# 3_FPGA.net
KiCad netlist of a schematic drawn in Altium Designer
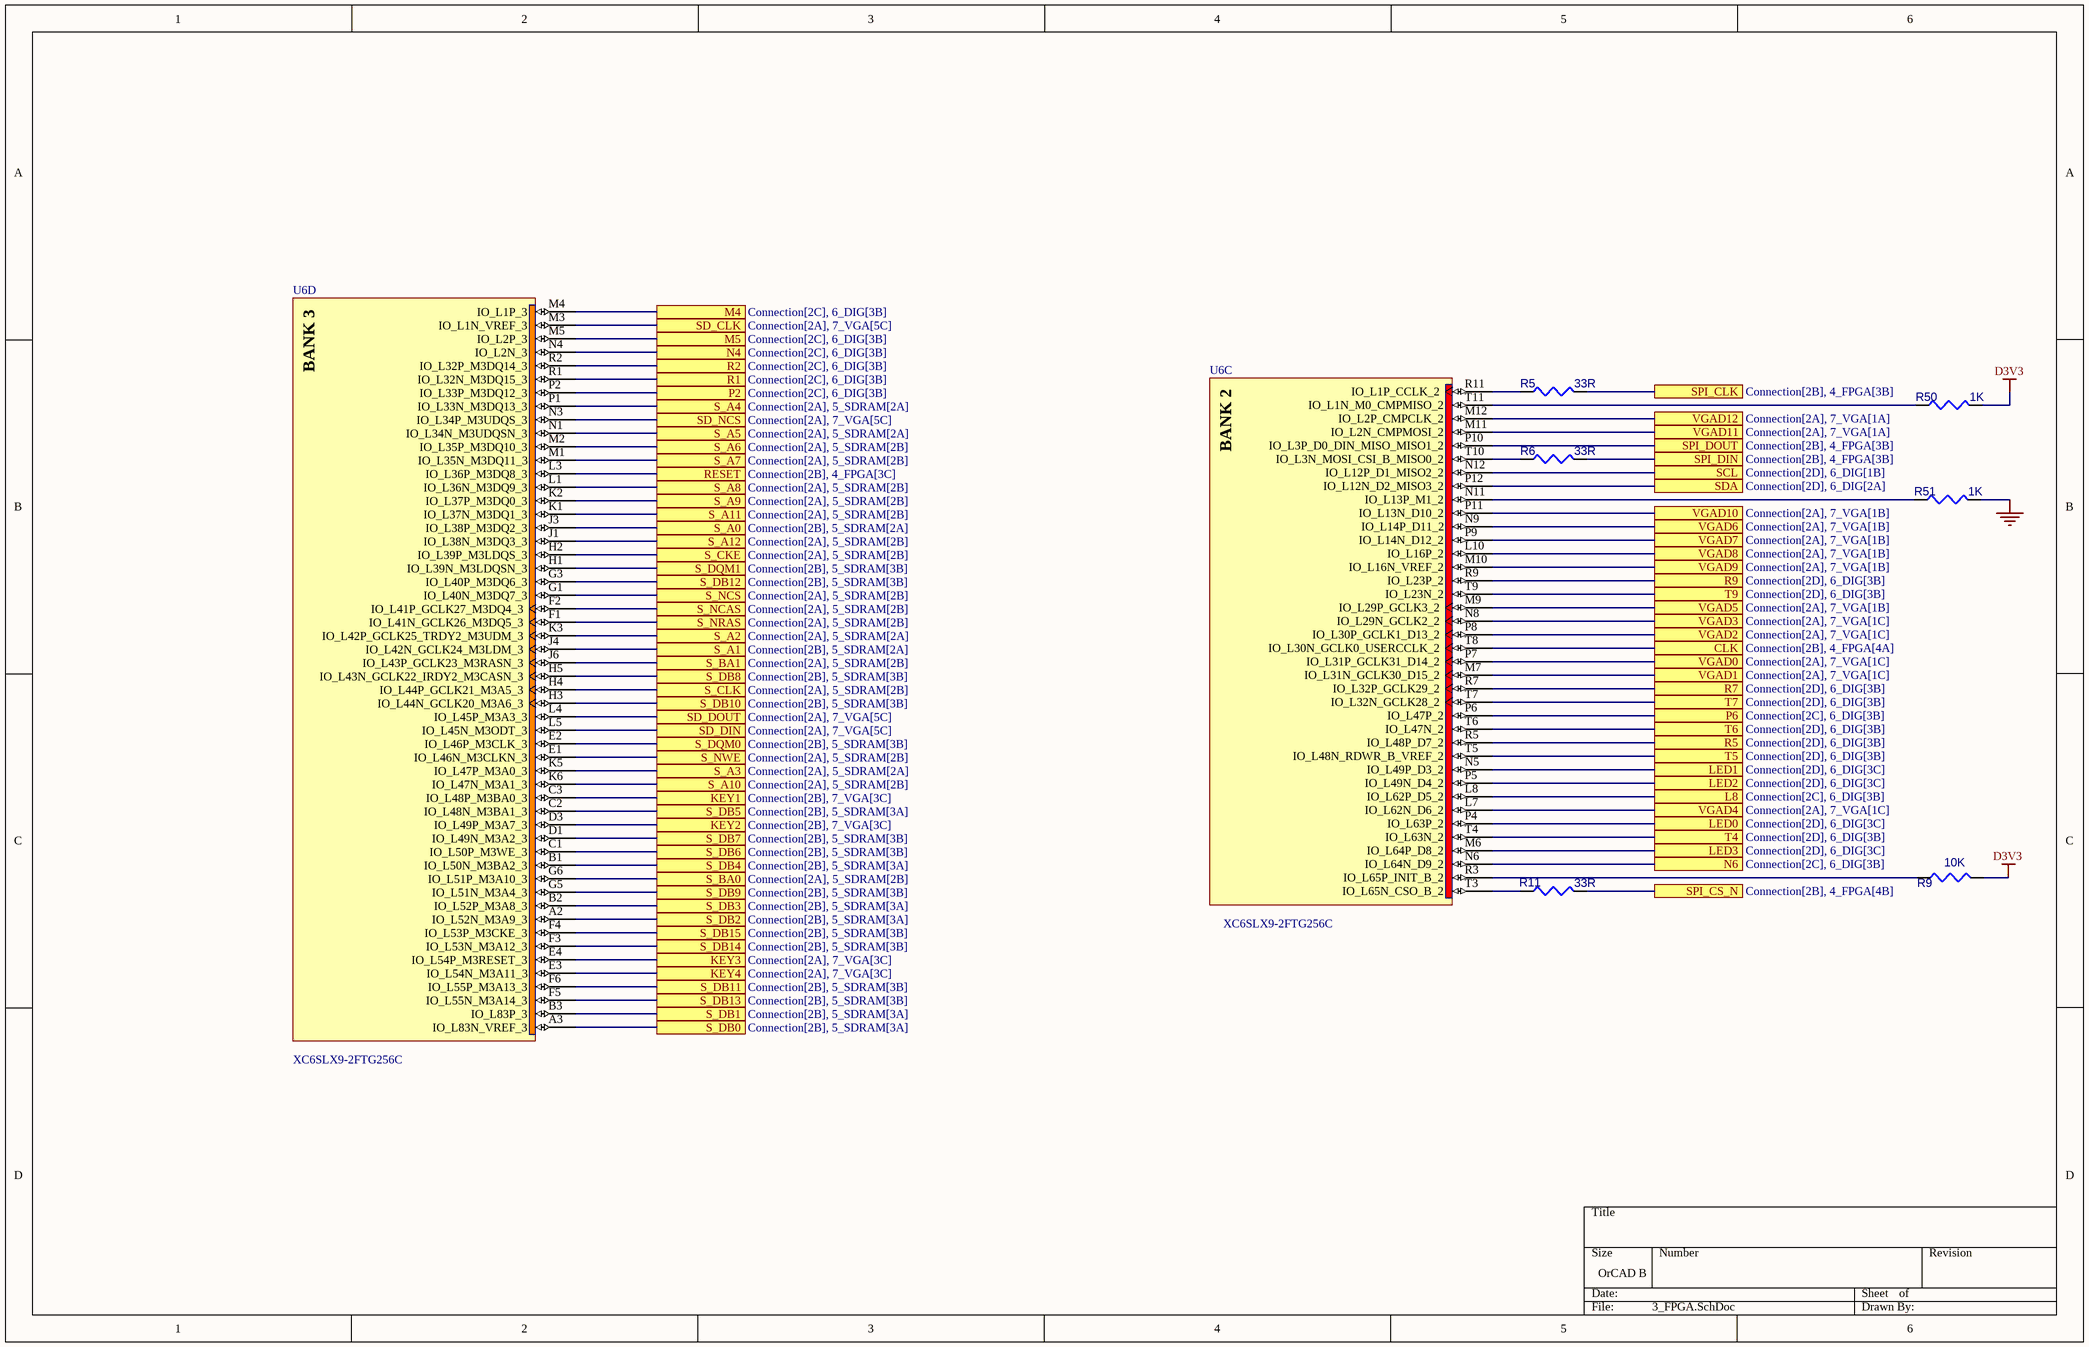
[diagram p0: 3_FPGA.SchDoc]

(export (version "E")
  (design (tool "Eeschema 10.0.6"))
  (components
    (comp (ref "R5") (value "33R") (footprint "0603") (libsource (lib "*") (part "R_Dup3")))
    (comp (ref "R6") (value "33R") (footprint "0603") (libsource (lib "*") (part "R_Dup3")))
    (comp (ref "R9") (value "10K") (footprint "0603") (libsource (lib "*") (part "R_Dup1")))
    (comp (ref "R11") (value "33R") (footprint "0603") (libsource (lib "*") (part "R_Dup3")))
    (comp (ref "R50") (value "1K") (footprint "0603") (libsource (lib "*") (part "R")))
    (comp (ref "R51") (value "1K") (footprint "0603") (libsource (lib "*") (part "R")))
    (comp (ref "U6")
      (value "XC6SLX9-2FTG256C")
      (footprint "FTG256")
      (libsource (lib "Xilinx Spartan-6") (part "XC6SLX9-2FTG256C"))
    )
  )
  (nets
    (net (code "1") (name "/CLK") (class "Default")
      (node (ref "U6") (pin "T8") (pinfunction "IO_L30N_GCLK0_USERCCLK_2_T8") (pintype "bidirectional"))
    )
    (net (code "2") (name "/KEY1") (class "Default")
      (node (ref "U6") (pin "C3") (pinfunction "IO_L48P_M3BA0_3_C3") (pintype "bidirectional"))
    )
    (net (code "3") (name "/KEY2") (class "Default")
      (node (ref "U6") (pin "D3") (pinfunction "IO_L49P_M3A7_3_D3") (pintype "bidirectional"))
    )
    (net (code "4") (name "/KEY3") (class "Default")
      (node (ref "U6") (pin "E4") (pinfunction "IO_L54P_M3RESET_3_E4") (pintype "bidirectional"))
    )
    (net (code "5") (name "/KEY4") (class "Default")
      (node (ref "U6") (pin "E3") (pinfunction "IO_L54N_M3A11_3_E3") (pintype "bidirectional"))
    )
    (net (code "6") (name "/L8") (class "Default")
      (node (ref "U6") (pin "L8") (pinfunction "IO_L62P_D5_2_L8") (pintype "bidirectional"))
    )
    (net (code "7") (name "/LED0") (class "Default")
      (node (ref "U6") (pin "P4") (pinfunction "IO_L63P_2_P4") (pintype "bidirectional"))
    )
    (net (code "8") (name "/LED1") (class "Default")
      (node (ref "U6") (pin "N5") (pinfunction "IO_L49P_D3_2_N5") (pintype "bidirectional"))
    )
    (net (code "9") (name "/LED2") (class "Default")
      (node (ref "U6") (pin "P5") (pinfunction "IO_L49N_D4_2_P5") (pintype "bidirectional"))
    )
    (net (code "10") (name "/LED3") (class "Default")
      (node (ref "U6") (pin "M6") (pinfunction "IO_L64P_D8_2_M6") (pintype "bidirectional"))
    )
    (net (code "11") (name "/M4") (class "Default")
      (node (ref "U6") (pin "M4") (pinfunction "IO_L1P_3_M4") (pintype "bidirectional"))
    )
    (net (code "12") (name "/M5") (class "Default")
      (node (ref "U6") (pin "M5") (pinfunction "IO_L2P_3_M5") (pintype "bidirectional"))
    )
    (net (code "13") (name "/N4") (class "Default")
      (node (ref "U6") (pin "N4") (pinfunction "IO_L2N_3_N4") (pintype "bidirectional"))
    )
    (net (code "14") (name "/N6") (class "Default")
      (node (ref "U6") (pin "N6") (pinfunction "IO_L64N_D9_2_N6") (pintype "bidirectional"))
    )
    (net (code "15") (name "/P2") (class "Default")
      (node (ref "U6") (pin "P2") (pinfunction "IO_L33P_M3DQ12_3_P2") (pintype "bidirectional"))
    )
    (net (code "16") (name "/P6") (class "Default")
      (node (ref "U6") (pin "P6") (pinfunction "IO_L47P_2_P6") (pintype "bidirectional"))
    )
    (net (code "17") (name "/R1") (class "Default")
      (node (ref "U6") (pin "R1") (pinfunction "IO_L32N_M3DQ15_3_R1") (pintype "bidirectional"))
    )
    (net (code "18") (name "/R2") (class "Default")
      (node (ref "U6") (pin "R2") (pinfunction "IO_L32P_M3DQ14_3_R2") (pintype "bidirectional"))
    )
    (net (code "19") (name "/R5") (class "Default")
      (node (ref "U6") (pin "R5") (pinfunction "IO_L48P_D7_2_R5") (pintype "bidirectional"))
    )
    (net (code "20") (name "/R7") (class "Default")
      (node (ref "U6") (pin "R7") (pinfunction "IO_L32P_GCLK29_2_R7") (pintype "bidirectional"))
    )
    (net (code "21") (name "/R9") (class "Default")
      (node (ref "U6") (pin "R9") (pinfunction "IO_L23P_2_R9") (pintype "bidirectional"))
    )
    (net (code "22") (name "/RESET") (class "Default")
      (node (ref "U6") (pin "L3") (pinfunction "IO_L36P_M3DQ8_3_L3") (pintype "bidirectional"))
    )
    (net (code "23") (name "/SCL") (class "Default")
      (node (ref "U6") (pin "N12") (pinfunction "IO_L12P_D1_MISO2_2_N12") (pintype "bidirectional"))
    )
    (net (code "24") (name "/SDA") (class "Default")
      (node (ref "U6") (pin "P12") (pinfunction "IO_L12N_D2_MISO3_2_P12") (pintype "bidirectional"))
    )
    (net (code "25") (name "/SD_CLK") (class "Default")
      (node (ref "U6") (pin "M3") (pinfunction "IO_L1N_VREF_3_M3") (pintype "bidirectional"))
    )
    (net (code "26") (name "/SD_DIN") (class "Default")
      (node (ref "U6") (pin "L5") (pinfunction "IO_L45N_M3ODT_3_L5") (pintype "bidirectional"))
    )
    (net (code "27") (name "/SD_DOUT") (class "Default")
      (node (ref "U6") (pin "L4") (pinfunction "IO_L45P_M3A3_3_L4") (pintype "bidirectional"))
    )
    (net (code "28") (name "/SD_NCS") (class "Default")
      (node (ref "U6") (pin "N3") (pinfunction "IO_L34P_M3UDQS_3_N3") (pintype "bidirectional"))
    )
    (net (code "29") (name "/SPI_CLK") (class "Default")
      (node (ref "R5") (pin "2") (pinfunction "2_2") (pintype "passive"))
    )
    (net (code "30") (name "/SPI_CS_N") (class "Default")
      (node (ref "R11") (pin "2") (pinfunction "2_2") (pintype "passive"))
    )
    (net (code "31") (name "/SPI_DIN") (class "Default")
      (node (ref "R6") (pin "2") (pinfunction "2_2") (pintype "passive"))
    )
    (net (code "32") (name "/SPI_DOUT") (class "Default")
      (node (ref "U6") (pin "P10") (pinfunction "IO_L3P_D0_DIN_MISO_MISO1_2_P10") (pintype "bidirectional"))
    )
    (net (code "33") (name "/S_A0") (class "Default")
      (node (ref "U6") (pin "J3") (pinfunction "IO_L38P_M3DQ2_3_J3") (pintype "bidirectional"))
    )
    (net (code "34") (name "/S_A1") (class "Default")
      (node (ref "U6") (pin "J4") (pinfunction "IO_L42N_GCLK24_M3LDM_3_J4") (pintype "bidirectional"))
    )
    (net (code "35") (name "/S_A2") (class "Default")
      (node (ref "U6") (pin "K3") (pinfunction "IO_L42P_GCLK25_TRDY2_M3UDM_3_K3") (pintype "bidirectional"))
    )
    (net (code "36") (name "/S_A3") (class "Default")
      (node (ref "U6") (pin "K5") (pinfunction "IO_L47P_M3A0_3_K5") (pintype "bidirectional"))
    )
    (net (code "37") (name "/S_A4") (class "Default")
      (node (ref "U6") (pin "P1") (pinfunction "IO_L33N_M3DQ13_3_P1") (pintype "bidirectional"))
    )
    (net (code "38") (name "/S_A5") (class "Default")
      (node (ref "U6") (pin "N1") (pinfunction "IO_L34N_M3UDQSN_3_N1") (pintype "bidirectional"))
    )
    (net (code "39") (name "/S_A6") (class "Default")
      (node (ref "U6") (pin "M2") (pinfunction "IO_L35P_M3DQ10_3_M2") (pintype "bidirectional"))
    )
    (net (code "40") (name "/S_A7") (class "Default")
      (node (ref "U6") (pin "M1") (pinfunction "IO_L35N_M3DQ11_3_M1") (pintype "bidirectional"))
    )
    (net (code "41") (name "/S_A8") (class "Default")
      (node (ref "U6") (pin "L1") (pinfunction "IO_L36N_M3DQ9_3_L1") (pintype "bidirectional"))
    )
    (net (code "42") (name "/S_A9") (class "Default")
      (node (ref "U6") (pin "K2") (pinfunction "IO_L37P_M3DQ0_3_K2") (pintype "bidirectional"))
    )
    (net (code "43") (name "/S_A10") (class "Default")
      (node (ref "U6") (pin "K6") (pinfunction "IO_L47N_M3A1_3_K6") (pintype "bidirectional"))
    )
    (net (code "44") (name "/S_A11") (class "Default")
      (node (ref "U6") (pin "K1") (pinfunction "IO_L37N_M3DQ1_3_K1") (pintype "bidirectional"))
    )
    (net (code "45") (name "/S_A12") (class "Default")
      (node (ref "U6") (pin "J1") (pinfunction "IO_L38N_M3DQ3_3_J1") (pintype "bidirectional"))
    )
    (net (code "46") (name "/S_BA0") (class "Default")
      (node (ref "U6") (pin "G6") (pinfunction "IO_L51P_M3A10_3_G6") (pintype "bidirectional"))
    )
    (net (code "47") (name "/S_BA1") (class "Default")
      (node (ref "U6") (pin "J6") (pinfunction "IO_L43P_GCLK23_M3RASN_3_J6") (pintype "bidirectional"))
    )
    (net (code "48") (name "/S_CKE") (class "Default")
      (node (ref "U6") (pin "H2") (pinfunction "IO_L39P_M3LDQS_3_H2") (pintype "bidirectional"))
    )
    (net (code "49") (name "/S_CLK") (class "Default")
      (node (ref "U6") (pin "H4") (pinfunction "IO_L44P_GCLK21_M3A5_3_H4") (pintype "bidirectional"))
    )
    (net (code "50") (name "/S_DB0") (class "Default")
      (node (ref "U6") (pin "A3") (pinfunction "IO_L83N_VREF_3_A3") (pintype "bidirectional"))
    )
    (net (code "51") (name "/S_DB1") (class "Default")
      (node (ref "U6") (pin "B3") (pinfunction "IO_L83P_3_B3") (pintype "bidirectional"))
    )
    (net (code "52") (name "/S_DB2") (class "Default")
      (node (ref "U6") (pin "A2") (pinfunction "IO_L52N_M3A9_3_A2") (pintype "bidirectional"))
    )
    (net (code "53") (name "/S_DB3") (class "Default")
      (node (ref "U6") (pin "B2") (pinfunction "IO_L52P_M3A8_3_B2") (pintype "bidirectional"))
    )
    (net (code "54") (name "/S_DB4") (class "Default")
      (node (ref "U6") (pin "B1") (pinfunction "IO_L50N_M3BA2_3_B1") (pintype "bidirectional"))
    )
    (net (code "55") (name "/S_DB5") (class "Default")
      (node (ref "U6") (pin "C2") (pinfunction "IO_L48N_M3BA1_3_C2") (pintype "bidirectional"))
    )
    (net (code "56") (name "/S_DB6") (class "Default")
      (node (ref "U6") (pin "C1") (pinfunction "IO_L50P_M3WE_3_C1") (pintype "bidirectional"))
    )
    (net (code "57") (name "/S_DB7") (class "Default")
      (node (ref "U6") (pin "D1") (pinfunction "IO_L49N_M3A2_3_D1") (pintype "bidirectional"))
    )
    (net (code "58") (name "/S_DB8") (class "Default")
      (node (ref "U6") (pin "H5") (pinfunction "IO_L43N_GCLK22_IRDY2_M3CASN_3_H5") (pintype "bidirectional"))
    )
    (net (code "59") (name "/S_DB9") (class "Default")
      (node (ref "U6") (pin "G5") (pinfunction "IO_L51N_M3A4_3_G5") (pintype "bidirectional"))
    )
    (net (code "60") (name "/S_DB10") (class "Default")
      (node (ref "U6") (pin "H3") (pinfunction "IO_L44N_GCLK20_M3A6_3_H3") (pintype "bidirectional"))
    )
    (net (code "61") (name "/S_DB11") (class "Default")
      (node (ref "U6") (pin "F6") (pinfunction "IO_L55P_M3A13_3_F6") (pintype "bidirectional"))
    )
    (net (code "62") (name "/S_DB12") (class "Default")
      (node (ref "U6") (pin "G3") (pinfunction "IO_L40P_M3DQ6_3_G3") (pintype "bidirectional"))
    )
    (net (code "63") (name "/S_DB13") (class "Default")
      (node (ref "U6") (pin "F5") (pinfunction "IO_L55N_M3A14_3_F5") (pintype "bidirectional"))
    )
    (net (code "64") (name "/S_DB14") (class "Default")
      (node (ref "U6") (pin "F3") (pinfunction "IO_L53N_M3A12_3_F3") (pintype "bidirectional"))
    )
    (net (code "65") (name "/S_DB15") (class "Default")
      (node (ref "U6") (pin "F4") (pinfunction "IO_L53P_M3CKE_3_F4") (pintype "bidirectional"))
    )
    (net (code "66") (name "/S_DQM0") (class "Default")
      (node (ref "U6") (pin "E2") (pinfunction "IO_L46P_M3CLK_3_E2") (pintype "bidirectional"))
    )
    (net (code "67") (name "/S_DQM1") (class "Default")
      (node (ref "U6") (pin "H1") (pinfunction "IO_L39N_M3LDQSN_3_H1") (pintype "bidirectional"))
    )
    (net (code "68") (name "/S_NCAS") (class "Default")
      (node (ref "U6") (pin "F2") (pinfunction "IO_L41P_GCLK27_M3DQ4_3_F2") (pintype "bidirectional"))
    )
    (net (code "69") (name "/S_NCS") (class "Default")
      (node (ref "U6") (pin "G1") (pinfunction "IO_L40N_M3DQ7_3_G1") (pintype "bidirectional"))
    )
    (net (code "70") (name "/S_NRAS") (class "Default")
      (node (ref "U6") (pin "F1") (pinfunction "IO_L41N_GCLK26_M3DQ5_3_F1") (pintype "bidirectional"))
    )
    (net (code "71") (name "/S_NWE") (class "Default")
      (node (ref "U6") (pin "E1") (pinfunction "IO_L46N_M3CLKN_3_E1") (pintype "bidirectional"))
    )
    (net (code "72") (name "/T4") (class "Default")
      (node (ref "U6") (pin "T4") (pinfunction "IO_L63N_2_T4") (pintype "bidirectional"))
    )
    (net (code "73") (name "/T5") (class "Default")
      (node (ref "U6") (pin "T5") (pinfunction "IO_L48N_RDWR_B_VREF_2_T5") (pintype "bidirectional"))
    )
    (net (code "74") (name "/T6") (class "Default")
      (node (ref "U6") (pin "T6") (pinfunction "IO_L47N_2_T6") (pintype "bidirectional"))
    )
    (net (code "75") (name "/T7") (class "Default")
      (node (ref "U6") (pin "T7") (pinfunction "IO_L32N_GCLK28_2_T7") (pintype "bidirectional"))
    )
    (net (code "76") (name "/T9") (class "Default")
      (node (ref "U6") (pin "T9") (pinfunction "IO_L23N_2_T9") (pintype "bidirectional"))
    )
    (net (code "77") (name "/VGAD0") (class "Default")
      (node (ref "U6") (pin "P7") (pinfunction "IO_L31P_GCLK31_D14_2_P7") (pintype "bidirectional"))
    )
    (net (code "78") (name "/VGAD1") (class "Default")
      (node (ref "U6") (pin "M7") (pinfunction "IO_L31N_GCLK30_D15_2_M7") (pintype "bidirectional"))
    )
    (net (code "79") (name "/VGAD2") (class "Default")
      (node (ref "U6") (pin "P8") (pinfunction "IO_L30P_GCLK1_D13_2_P8") (pintype "bidirectional"))
    )
    (net (code "80") (name "/VGAD3") (class "Default")
      (node (ref "U6") (pin "N8") (pinfunction "IO_L29N_GCLK2_2_N8") (pintype "bidirectional"))
    )
    (net (code "81") (name "/VGAD4") (class "Default")
      (node (ref "U6") (pin "L7") (pinfunction "IO_L62N_D6_2_L7") (pintype "bidirectional"))
    )
    (net (code "82") (name "/VGAD5") (class "Default")
      (node (ref "U6") (pin "M9") (pinfunction "IO_L29P_GCLK3_2_M9") (pintype "bidirectional"))
    )
    (net (code "83") (name "/VGAD6") (class "Default")
      (node (ref "U6") (pin "N9") (pinfunction "IO_L14P_D11_2_N9") (pintype "bidirectional"))
    )
    (net (code "84") (name "/VGAD7") (class "Default")
      (node (ref "U6") (pin "P9") (pinfunction "IO_L14N_D12_2_P9") (pintype "bidirectional"))
    )
    (net (code "85") (name "/VGAD8") (class "Default")
      (node (ref "U6") (pin "L10") (pinfunction "IO_L16P_2_L10") (pintype "bidirectional"))
    )
    (net (code "86") (name "/VGAD9") (class "Default")
      (node (ref "U6") (pin "M10") (pinfunction "IO_L16N_VREF_2_M10") (pintype "bidirectional"))
    )
    (net (code "87") (name "/VGAD10") (class "Default")
      (node (ref "U6") (pin "P11") (pinfunction "IO_L13N_D10_2_P11") (pintype "bidirectional"))
    )
    (net (code "88") (name "/VGAD11") (class "Default")
      (node (ref "U6") (pin "M11") (pinfunction "IO_L2N_CMPMOSI_2_M11") (pintype "bidirectional"))
    )
    (net (code "89") (name "/VGAD12") (class "Default")
      (node (ref "U6") (pin "M12") (pinfunction "IO_L2P_CMPCLK_2_M12") (pintype "bidirectional"))
    )
    (net (code "90") (name "D3V3") (class "Default")
      (node (ref "R50") (pin "2") (pinfunction "2_2") (pintype "passive"))
      (node (ref "R9") (pin "2") (pinfunction "2_2") (pintype "passive"))
    )
    (net (code "91") (name "GND") (class "Default")
      (node (ref "R51") (pin "2") (pinfunction "2_2") (pintype "passive"))
    )
    (net (code "92") (name "Net-(U6C-IO_L1N_M0_CMPMISO_2)") (class "Default")
      (node (ref "R50") (pin "1") (pinfunction "1_1") (pintype "passive"))
      (node (ref "U6") (pin "T11") (pinfunction "IO_L1N_M0_CMPMISO_2_T11") (pintype "bidirectional"))
    )
    (net (code "93") (name "Net-(U6C-IO_L1P_CCLK_2)") (class "Default")
      (node (ref "R5") (pin "1") (pinfunction "1_1") (pintype "passive"))
      (node (ref "U6") (pin "R11") (pinfunction "IO_L1P_CCLK_2_R11") (pintype "bidirectional"))
    )
    (net (code "94") (name "Net-(U6C-IO_L3N_MOSI_CSI_B_MISO0_2)") (class "Default")
      (node (ref "R6") (pin "1") (pinfunction "1_1") (pintype "passive"))
      (node (ref "U6") (pin "T10") (pinfunction "IO_L3N_MOSI_CSI_B_MISO0_2_T10") (pintype "bidirectional"))
    )
    (net (code "95") (name "Net-(U6C-IO_L13P_M1_2)") (class "Default")
      (node (ref "R51") (pin "1") (pinfunction "1_1") (pintype "passive"))
      (node (ref "U6") (pin "N11") (pinfunction "IO_L13P_M1_2_N11") (pintype "bidirectional"))
    )
    (net (code "96") (name "Net-(U6C-IO_L65N_CSO_B_2)") (class "Default")
      (node (ref "R11") (pin "1") (pinfunction "1_1") (pintype "passive"))
      (node (ref "U6") (pin "T3") (pinfunction "IO_L65N_CSO_B_2_T3") (pintype "bidirectional"))
    )
    (net (code "97") (name "Net-(U6C-IO_L65P_INIT_B_2)") (class "Default")
      (node (ref "R9") (pin "1") (pinfunction "1_1") (pintype "passive"))
      (node (ref "U6") (pin "R3") (pinfunction "IO_L65P_INIT_B_2_R3") (pintype "bidirectional"))
    )
  )
)
